# Mjolnir.net
KiCad netlist of a schematic drawn in EAGLE
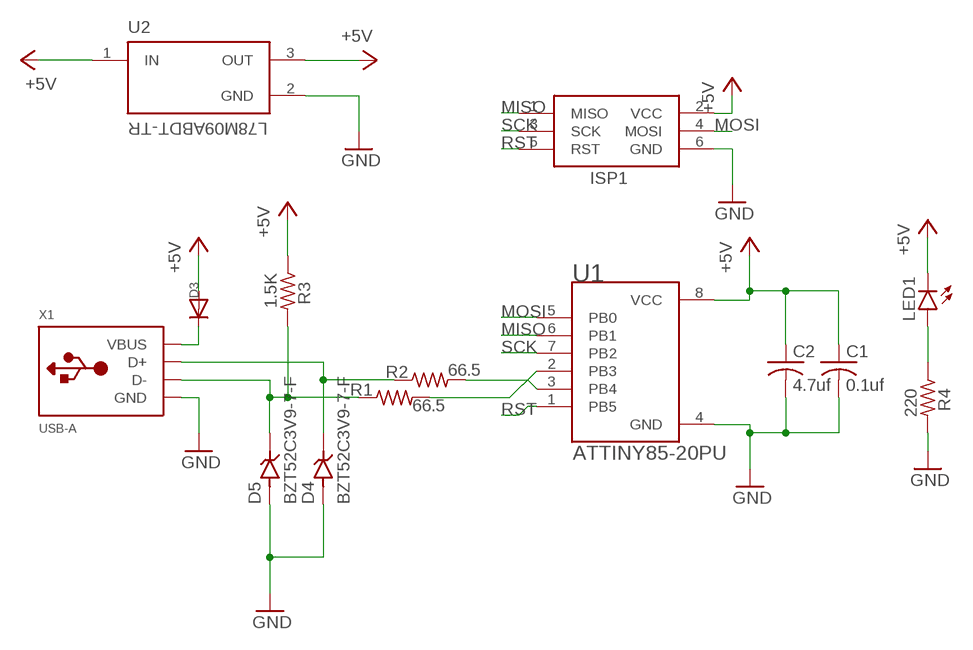
[diagram p0: schematic, sheet 1]

(export (version "E")
  (design (tool "Eeschema 10.0.6"))
  (components
    (comp (ref "C1")
      (value "0.1uf")
      (footprint "eagle-import:C0805")
      (libsource (lib "eagle-import") (part "C-USC0805"))
    )
    (comp (ref "C2")
      (value "4.7uf")
      (footprint "eagle-import:C0805")
      (libsource (lib "eagle-import") (part "C-USC0805"))
    )
    (comp (ref "D3")
      (value "DIODESOD-123")
      (footprint "eagle-import:SOD-123")
      (libsource (lib "eagle-import") (part "DIODESOD-123"))
    )
    (comp (ref "D4")
      (value "BZT52C3V9-7-F")
      (footprint "eagle-import:SOD3715X145N")
      (fields (field (name "MF") "Diodes Inc."))
      (libsource (lib "eagle-import") (part "BZT52C3V9-7-F"))
    )
    (comp (ref "D5")
      (value "BZT52C3V9-7-F")
      (footprint "eagle-import:SOD3715X145N")
      (fields (field (name "MF") "Diodes Inc."))
      (libsource (lib "eagle-import") (part "BZT52C3V9-7-F"))
    )
    (comp (ref "ISP1")
      (value "AVRISP-6")
      (footprint "eagle-import:AVRISP")
      (libsource (lib "eagle-import") (part "AVRISP-6"))
    )
    (comp (ref "LED1")
      (value "LEDCHIPLED_0805")
      (footprint "eagle-import:CHIPLED_0805")
      (libsource (lib "eagle-import") (part "LEDCHIPLED_0805"))
    )
    (comp (ref "R1")
      (value "66.5")
      (footprint "eagle-import:R0805")
      (libsource (lib "eagle-import") (part "R-US_R0805"))
    )
    (comp (ref "R2")
      (value "66.5")
      (footprint "eagle-import:R0805")
      (libsource (lib "eagle-import") (part "R-US_R0805"))
    )
    (comp (ref "R3")
      (value "1.5K")
      (footprint "eagle-import:R0805")
      (libsource (lib "eagle-import") (part "R-US_R0805"))
    )
    (comp (ref "R4")
      (value "220")
      (footprint "eagle-import:R0805")
      (libsource (lib "eagle-import") (part "R-US_R0805"))
    )
    (comp (ref "U1")
      (value "ATTINY85-20PU")
      (footprint "eagle-import:DIP762W46P254L927H533Q8B")
      (fields (field (name "MF") "Microchip Technology"))
      (libsource (lib "eagle-import") (part "ATTINY85-20PU"))
    )
    (comp (ref "U2")
      (value "L78M09ABDT-TR")
      (footprint "eagle-import:VREG_L78M09ABDT-TR")
      (fields (field (name "MF") "STMicroelectronics"))
      (libsource (lib "eagle-import") (part "L78M09ABDT-TR"))
    )
    (comp (ref "X1")
      (value "USB-A")
      (footprint "eagle-import:MOLEX_480371000")
      (libsource (lib "eagle-import") (part "USB-A"))
    )
  )
  (nets
    (net (code "1") (name "+5V") (class "Default")
      (node (ref "C1") (pin "1") (pinfunction "1_1") (pintype "passive"))
      (node (ref "C2") (pin "1") (pinfunction "1_1") (pintype "passive"))
      (node (ref "D3") (pin "A") (pinfunction "A_A") (pintype "passive"))
      (node (ref "ISP1") (pin "2") (pinfunction "VCC_2") (pintype "power_in"))
      (node (ref "LED1") (pin "C") (pinfunction "C_C") (pintype "passive"))
      (node (ref "R3") (pin "1") (pinfunction "1_1") (pintype "passive"))
      (node (ref "U1") (pin "8") (pinfunction "VCC_8") (pintype "power_in"))
      (node (ref "U2") (pin "1") (pinfunction "IN_1") (pintype "input"))
      (node (ref "U2") (pin "3") (pinfunction "OUT_3") (pintype "output"))
    )
    (net (code "2") (name "/MISO") (class "Default")
      (node (ref "ISP1") (pin "1") (pinfunction "MISO_1") (pintype "input"))
      (node (ref "U1") (pin "6") (pinfunction "PB1_6") (pintype "bidirectional"))
    )
    (net (code "3") (name "/MOSI") (class "Default")
      (node (ref "ISP1") (pin "4") (pinfunction "MOSI_4") (pintype "output"))
      (node (ref "U1") (pin "5") (pinfunction "PB0_5") (pintype "bidirectional"))
    )
    (net (code "4") (name "/RST") (class "Default")
      (node (ref "ISP1") (pin "5") (pinfunction "RST_5") (pintype "output"))
      (node (ref "U1") (pin "1") (pinfunction "PB5_1") (pintype "bidirectional"))
    )
    (net (code "5") (name "/SCK") (class "Default")
      (node (ref "ISP1") (pin "3") (pinfunction "SCK_3") (pintype "output"))
      (node (ref "U1") (pin "7") (pinfunction "PB2_7") (pintype "bidirectional"))
    )
    (net (code "6") (name "GND") (class "Default")
      (node (ref "C1") (pin "2") (pinfunction "2_2") (pintype "passive"))
      (node (ref "C2") (pin "2") (pinfunction "2_2") (pintype "passive"))
      (node (ref "D4") (pin "A") (pinfunction "A_A") (pintype "passive"))
      (node (ref "D5") (pin "A") (pinfunction "A_A") (pintype "passive"))
      (node (ref "ISP1") (pin "6") (pinfunction "GND_6") (pintype "power_in"))
      (node (ref "R4") (pin "2") (pinfunction "2_2") (pintype "passive"))
      (node (ref "U1") (pin "4") (pinfunction "GND_4") (pintype "power_in"))
      (node (ref "U2") (pin "2") (pinfunction "GND_2") (pintype "power_in"))
      (node (ref "X1") (pin "4") (pinfunction "GND_4") (pintype "power_in"))
    )
    (net (code "7") (name "Net-(LED1-PadA)") (class "Default")
      (node (ref "LED1") (pin "A") (pinfunction "A_A") (pintype "passive"))
      (node (ref "R4") (pin "1") (pinfunction "1_1") (pintype "passive"))
    )
    (net (code "8") (name "Net-(U1-PB3)") (class "Default")
      (node (ref "R1") (pin "2") (pinfunction "2_2") (pintype "passive"))
      (node (ref "U1") (pin "2") (pinfunction "PB3_2") (pintype "bidirectional"))
    )
    (net (code "9") (name "Net-(U1-PB4)") (class "Default")
      (node (ref "R2") (pin "2") (pinfunction "2_2") (pintype "passive"))
      (node (ref "U1") (pin "3") (pinfunction "PB4_3") (pintype "bidirectional"))
    )
    (net (code "10") (name "Net-(X1-D+)") (class "Default")
      (node (ref "D4") (pin "C") (pinfunction "C_C") (pintype "passive"))
      (node (ref "R2") (pin "1") (pinfunction "1_1") (pintype "passive"))
      (node (ref "X1") (pin "3") (pinfunction "D+_3") (pintype "bidirectional"))
    )
    (net (code "11") (name "Net-(X1-D-)") (class "Default")
      (node (ref "D5") (pin "C") (pinfunction "C_C") (pintype "passive"))
      (node (ref "R1") (pin "1") (pinfunction "1_1") (pintype "passive"))
      (node (ref "R3") (pin "2") (pinfunction "2_2") (pintype "passive"))
      (node (ref "X1") (pin "2") (pinfunction "D-_2") (pintype "bidirectional"))
    )
    (net (code "12") (name "Net-(X1-VBUS)") (class "Default")
      (node (ref "D3") (pin "C") (pinfunction "C_C") (pintype "passive"))
      (node (ref "X1") (pin "1") (pinfunction "VBUS_1") (pintype "power_in"))
    )
  )
)
